# Drone.net
KiCad netlist of a schematic drawn in Altium Designer
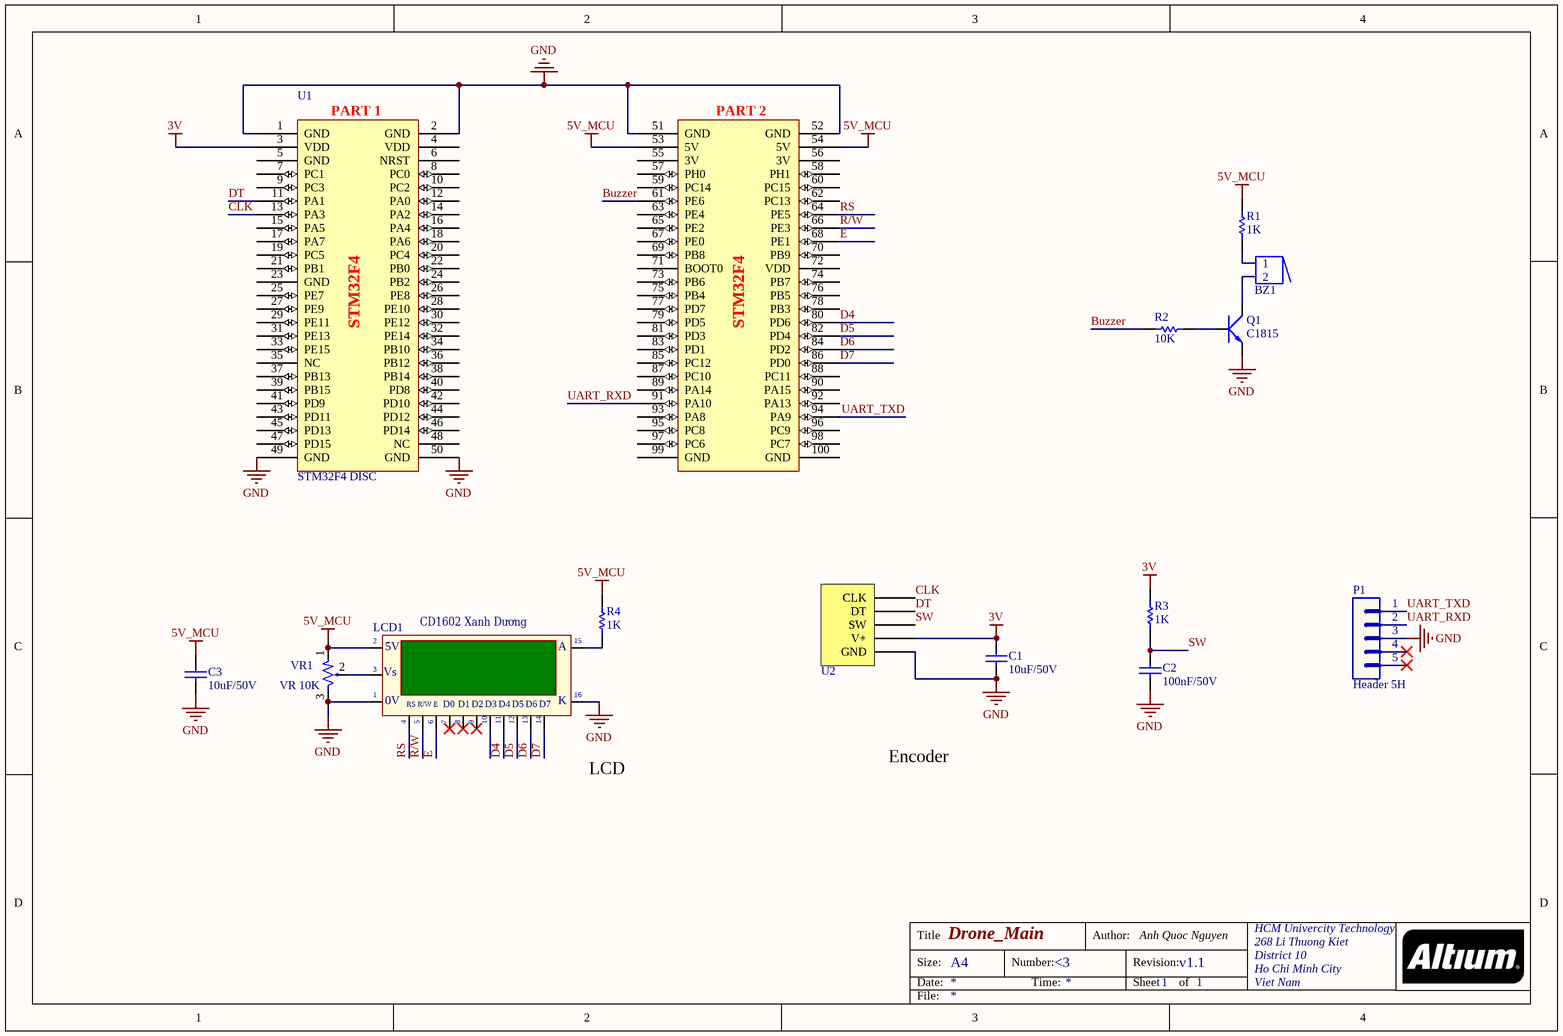
[diagram p0: Drone.SchDoc]

(export (version "E")
  (design (tool "Eeschema 10.0.6"))
  (components
    (comp (ref "BZ1") (value "Buzzer") (footprint "BUZZER") (libsource (lib "xecanbang") (part "Buzzer")))
    (comp (ref "C1")
      (value "10uF/50V")
      (footprint "CAP-SM-0805")
      (description "CAP CER 10UF 50V X5R 0805")
      (fields
        (field (name "MANUFACTURER") "Yageo")
        (field (name "MANUFACTURER PART NUMBER") "CC0805KKX5R9BB106")
      )
      (libsource (lib "Capacitor") (part "Cap-10uF-50V-0805"))
    )
    (comp (ref "C2")
      (value "100nF/50V")
      (footprint "CAP-SM-0805")
      (description "CAP CER 0.1UF 50V Y5V 0805")
      (fields
        (field (name "MANUFACTURER") "Samsung Electro-Mechanics")
        (field (name "MANUFACTURER PART NUMBER") "CL21F104ZBCNNNC")
      )
      (libsource (lib "Capacitor") (part "Cap-100nF-50V-0805"))
    )
    (comp (ref "C3")
      (value "10uF/50V")
      (footprint "CAP-SM-0805")
      (description "CAP CER 10UF 50V X5R 0805")
      (fields
        (field (name "MANUFACTURER") "Yageo")
        (field (name "MANUFACTURER PART NUMBER") "CC0805KKX5R9BB106")
      )
      (libsource (lib "Capacitor") (part "Cap-10uF-50V-0805"))
    )
    (comp (ref "LCD1")
      (value "CD1602 Xanh Dương")
      (footprint "LCD16X2")
      (description "Cắm")
      (libsource (lib "THU VIEN SCH") (part "LCD16x2A"))
    )
    (comp (ref "P1")
      (value "Header 5H")
      (footprint "JP5H")
      (description "Header, 5-Pin, Right Angle")
      (fields (field (name "PUBLISHER") "Altium Limited"))
      (libsource (lib "Header-connector") (part "Header 5H"))
    )
    (comp (ref "Q1")
      (value "C1815")
      (footprint "QTO-92")
      (description "Dán")
      (libsource (lib "THU VIEN SCH") (part "C1815"))
    )
    (comp (ref "R1")
      (value "1K")
      (footprint "Resistor:RES-SM-0805")
      (description "RES 1K OHM 1% 1/4W 0805")
      (fields
        (field (name "MANUFACTURER") "Stackpole Electronics Inc")
        (field (name "MANUFACTURER PART NUMBER") "RNCP0805FTD1K00")
      )
      (libsource (lib "Resistor") (part "Res-1K-0805"))
    )
    (comp (ref "R2")
      (value "10K")
      (footprint "Resistor:RES-SM-0805")
      (description "RES 10K OHM 1% 1/4W 0805")
      (fields
        (field (name "MANUFACTURER") "Stackpole Electronics Inc")
        (field (name "MANUFACTURER PART NUMBER") "RNCP0805FTD10K0")
      )
      (libsource (lib "Resistor") (part "Res-10k-0805"))
    )
    (comp (ref "R3")
      (value "1K")
      (footprint "Resistor:RES-SM-0805")
      (description "RES 1K OHM 1% 1/4W 0805")
      (fields
        (field (name "MANUFACTURER") "Stackpole Electronics Inc")
        (field (name "MANUFACTURER PART NUMBER") "RNCP0805FTD1K00")
      )
      (libsource (lib "Resistor") (part "Res-1K-0805"))
    )
    (comp (ref "R4")
      (value "1K")
      (footprint "Resistor:RES-SM-0805")
      (description "RES 1K OHM 1% 1/4W 0805")
      (fields
        (field (name "MANUFACTURER") "Stackpole Electronics Inc")
        (field (name "MANUFACTURER PART NUMBER") "RNCP0805FTD1K00")
      )
      (libsource (lib "Resistor") (part "Res-1K-0805"))
    )
    (comp (ref "U1")
      (value "STM32F4 DISC")
      (footprint "STM32F4 DISC")
      (description "STM32F4 Discovery board. Chip on Board is Stm32f411VET6. Speed is 150MHz")
      (libsource (lib "Drone") (part "STM32F4 DISC"))
    )
    (comp (ref "U2")
      (value "Rotary Encoder")
      (footprint "Rotary Encoder")
      (libsource (lib "Drone") (part "Rotary Encoder"))
    )
    (comp (ref "VR1")
      (value "VR 10K")
      (footprint "Varistor 1")
      (description "Var Resistor")
      (fields (field (name "Comment") "10K"))
      (libsource (lib "PIF_Library") (part "Var Resistor"))
    )
  )
  (nets
    (net (code "1") (name "/Buzzer") (class "Default")
      (node (ref "R2") (pin "1") (pinfunction "1_1") (pintype "passive"))
      (node (ref "U1") (pin "61") (pinfunction "PE6_61") (pintype "bidirectional"))
    )
    (net (code "2") (name "/CLK") (class "Default")
      (node (ref "U1") (pin "13") (pinfunction "PA3_13") (pintype "bidirectional"))
      (node (ref "U2") (pin "1") (pinfunction "CLK_1") (pintype "passive"))
    )
    (net (code "3") (name "/D4") (class "Default")
      (node (ref "LCD1") (pin "11") (pinfunction "D4_11") (pintype "passive"))
      (node (ref "U1") (pin "80") (pinfunction "PD6_80") (pintype "bidirectional"))
    )
    (net (code "4") (name "/D5") (class "Default")
      (node (ref "LCD1") (pin "12") (pinfunction "D5_12") (pintype "passive"))
      (node (ref "U1") (pin "82") (pinfunction "PD4_82") (pintype "bidirectional"))
    )
    (net (code "5") (name "/D6") (class "Default")
      (node (ref "LCD1") (pin "13") (pinfunction "D6_13") (pintype "passive"))
      (node (ref "U1") (pin "84") (pinfunction "PD2_84") (pintype "bidirectional"))
    )
    (net (code "6") (name "/D7") (class "Default")
      (node (ref "LCD1") (pin "14") (pinfunction "D7_14") (pintype "passive"))
      (node (ref "U1") (pin "86") (pinfunction "PD0_86") (pintype "bidirectional"))
    )
    (net (code "7") (name "/DT") (class "Default")
      (node (ref "U1") (pin "11") (pinfunction "PA1_11") (pintype "bidirectional"))
      (node (ref "U2") (pin "2") (pinfunction "DT_2") (pintype "passive"))
    )
    (net (code "8") (name "/E") (class "Default")
      (node (ref "LCD1") (pin "6") (pinfunction "~{EN}_6") (pintype "passive"))
      (node (ref "U1") (pin "68") (pinfunction "PE1_68") (pintype "bidirectional"))
    )
    (net (code "9") (name "/RS") (class "Default")
      (node (ref "LCD1") (pin "4") (pinfunction "RS_4") (pintype "passive"))
      (node (ref "U1") (pin "64") (pinfunction "PE5_64") (pintype "bidirectional"))
    )
    (net (code "10") (name "/R{slash}~{W}") (class "Default")
      (node (ref "LCD1") (pin "5") (pinfunction "R/~{W}_5") (pintype "passive"))
      (node (ref "U1") (pin "66") (pinfunction "PE3_66") (pintype "bidirectional"))
    )
    (net (code "11") (name "/SW") (class "Default")
      (node (ref "C2") (pin "2") (pinfunction "2_2") (pintype "passive"))
      (node (ref "R3") (pin "1") (pinfunction "1_1") (pintype "passive"))
      (node (ref "U2") (pin "3") (pinfunction "SW_3") (pintype "passive"))
    )
    (net (code "12") (name "/UART_RXD") (class "Default")
      (node (ref "P1") (pin "2") (pinfunction "2_2") (pintype "passive"))
      (node (ref "U1") (pin "91") (pinfunction "PA10_91") (pintype "bidirectional"))
    )
    (net (code "13") (name "/UART_TXD") (class "Default")
      (node (ref "P1") (pin "1") (pinfunction "1_1") (pintype "passive"))
      (node (ref "U1") (pin "94") (pinfunction "PA9_94") (pintype "bidirectional"))
    )
    (net (code "14") (name "3V") (class "Default")
      (node (ref "C1") (pin "1") (pinfunction "1_1") (pintype "passive"))
      (node (ref "R3") (pin "2") (pinfunction "2_2") (pintype "passive"))
      (node (ref "U1") (pin "3") (pinfunction "VDD_3") (pintype "power_in"))
      (node (ref "U2") (pin "4") (pinfunction "V+_4") (pintype "passive"))
    )
    (net (code "15") (name "5V_MCU") (class "Default")
      (node (ref "C3") (pin "1") (pinfunction "1_1") (pintype "passive"))
      (node (ref "LCD1") (pin "2") (pinfunction "VDD_2") (pintype "passive"))
      (node (ref "R1") (pin "2") (pinfunction "2_2") (pintype "passive"))
      (node (ref "R4") (pin "2") (pinfunction "2_2") (pintype "passive"))
      (node (ref "U1") (pin "53") (pinfunction "5V_53") (pintype "power_in"))
      (node (ref "U1") (pin "54") (pinfunction "5V_54") (pintype "power_in"))
      (node (ref "VR1") (pin "1") (pinfunction "1_1") (pintype "passive"))
    )
    (net (code "16") (name "GND") (class "Default")
      (node (ref "C1") (pin "2") (pinfunction "2_2") (pintype "passive"))
      (node (ref "C2") (pin "1") (pinfunction "1_1") (pintype "passive"))
      (node (ref "C3") (pin "2") (pinfunction "2_2") (pintype "passive"))
      (node (ref "LCD1") (pin "1") (pinfunction "GND_1") (pintype "passive"))
      (node (ref "LCD1") (pin "16") (pinfunction "K_16") (pintype "passive"))
      (node (ref "P1") (pin "3") (pinfunction "3_3") (pintype "passive"))
      (node (ref "Q1") (pin "3") (pinfunction "E_3") (pintype "passive"))
      (node (ref "U1") (pin "1") (pinfunction "GND_1") (pintype "power_in"))
      (node (ref "U1") (pin "2") (pinfunction "GND_2") (pintype "power_in"))
      (node (ref "U1") (pin "49") (pinfunction "GND_49") (pintype "power_in"))
      (node (ref "U1") (pin "50") (pinfunction "GND_50") (pintype "power_in"))
      (node (ref "U1") (pin "51") (pinfunction "GND_51") (pintype "power_in"))
      (node (ref "U1") (pin "52") (pinfunction "GND_52") (pintype "power_in"))
      (node (ref "U2") (pin "5") (pinfunction "GND_5") (pintype "passive"))
      (node (ref "VR1") (pin "3") (pinfunction "3_3") (pintype "passive"))
    )
    (net (code "17") (name "Net-(BZ1-Pad1)") (class "Default")
      (node (ref "BZ1") (pin "1") (pinfunction "1_1") (pintype "passive"))
      (node (ref "R1") (pin "1") (pinfunction "1_1") (pintype "passive"))
    )
    (net (code "18") (name "Net-(LCD1-A)") (class "Default")
      (node (ref "LCD1") (pin "15") (pinfunction "A_15") (pintype "passive"))
      (node (ref "R4") (pin "1") (pinfunction "1_1") (pintype "passive"))
    )
    (net (code "19") (name "Net-(LCD1-VEE)") (class "Default")
      (node (ref "LCD1") (pin "3") (pinfunction "VEE_3") (pintype "passive"))
      (node (ref "VR1") (pin "2") (pinfunction "2_2") (pintype "passive"))
    )
    (net (code "20") (name "Net-(Q1-B)") (class "Default")
      (node (ref "Q1") (pin "1") (pinfunction "B_1") (pintype "passive"))
      (node (ref "R2") (pin "2") (pinfunction "2_2") (pintype "passive"))
    )
    (net (code "21") (name "Net-(Q1-C)") (class "Default")
      (node (ref "BZ1") (pin "2") (pinfunction "2_2") (pintype "passive"))
      (node (ref "Q1") (pin "2") (pinfunction "C_2") (pintype "passive"))
    )
    (net (code "22") (name "unconnected-(LCD1-D0-Pad7)") (class "Default")
      (node (ref "LCD1") (pin "7") (pinfunction "D0_7") (pintype "passive+no_connect"))
    )
    (net (code "23") (name "unconnected-(LCD1-D1-Pad8)") (class "Default")
      (node (ref "LCD1") (pin "8") (pinfunction "D1_8") (pintype "passive+no_connect"))
    )
    (net (code "24") (name "unconnected-(LCD1-D2-Pad9)") (class "Default")
      (node (ref "LCD1") (pin "9") (pinfunction "D2_9") (pintype "passive+no_connect"))
    )
    (net (code "25") (name "unconnected-(LCD1-D3-Pad10)") (class "Default")
      (node (ref "LCD1") (pin "10") (pinfunction "D3_10") (pintype "passive"))
    )
    (net (code "26") (name "unconnected-(P1-Pad4)") (class "Default")
      (node (ref "P1") (pin "4") (pinfunction "4_4") (pintype "passive+no_connect"))
    )
    (net (code "27") (name "unconnected-(P1-Pad5)") (class "Default")
      (node (ref "P1") (pin "5") (pinfunction "5_5") (pintype "passive+no_connect"))
    )
    (net (code "28") (name "unconnected-(U1-3V-Pad55)") (class "Default")
      (node (ref "U1") (pin "55") (pinfunction "3V_55") (pintype "power_in"))
    )
    (net (code "29") (name "unconnected-(U1-3V-Pad56)") (class "Default")
      (node (ref "U1") (pin "56") (pinfunction "3V_56") (pintype "power_in"))
    )
    (net (code "30") (name "unconnected-(U1-BOOT0-Pad71)") (class "Default")
      (node (ref "U1") (pin "71") (pinfunction "BOOT0_71") (pintype "passive"))
    )
    (net (code "31") (name "unconnected-(U1-GND-Pad5)") (class "Default")
      (node (ref "U1") (pin "5") (pinfunction "GND_5") (pintype "power_in"))
    )
    (net (code "32") (name "unconnected-(U1-GND-Pad23)") (class "Default")
      (node (ref "U1") (pin "23") (pinfunction "GND_23") (pintype "power_in"))
    )
    (net (code "33") (name "unconnected-(U1-GND-Pad99)") (class "Default")
      (node (ref "U1") (pin "99") (pinfunction "GND_99") (pintype "power_in"))
    )
    (net (code "34") (name "unconnected-(U1-GND-Pad100)") (class "Default")
      (node (ref "U1") (pin "100") (pinfunction "GND_100") (pintype "power_in"))
    )
    (net (code "35") (name "unconnected-(U1-NC-Pad35)") (class "Default")
      (node (ref "U1") (pin "35") (pinfunction "NC_35") (pintype "passive"))
    )
    (net (code "36") (name "unconnected-(U1-NC-Pad48)") (class "Default")
      (node (ref "U1") (pin "48") (pinfunction "NC_48") (pintype "passive"))
    )
    (net (code "37") (name "unconnected-(U1-NRST-Pad6)") (class "Default")
      (node (ref "U1") (pin "6") (pinfunction "NRST_6") (pintype "passive"))
    )
    (net (code "38") (name "unconnected-(U1-PA0-Pad12)") (class "Default")
      (node (ref "U1") (pin "12") (pinfunction "PA0_12") (pintype "bidirectional"))
    )
    (net (code "39") (name "unconnected-(U1-PA2-Pad14)") (class "Default")
      (node (ref "U1") (pin "14") (pinfunction "PA2_14") (pintype "bidirectional"))
    )
    (net (code "40") (name "unconnected-(U1-PA4-Pad16)") (class "Default")
      (node (ref "U1") (pin "16") (pinfunction "PA4_16") (pintype "bidirectional"))
    )
    (net (code "41") (name "unconnected-(U1-PA5-Pad15)") (class "Default")
      (node (ref "U1") (pin "15") (pinfunction "PA5_15") (pintype "bidirectional"))
    )
    (net (code "42") (name "unconnected-(U1-PA6-Pad18)") (class "Default")
      (node (ref "U1") (pin "18") (pinfunction "PA6_18") (pintype "bidirectional"))
    )
    (net (code "43") (name "unconnected-(U1-PA7-Pad17)") (class "Default")
      (node (ref "U1") (pin "17") (pinfunction "PA7_17") (pintype "bidirectional"))
    )
    (net (code "44") (name "unconnected-(U1-PA8-Pad93)") (class "Default")
      (node (ref "U1") (pin "93") (pinfunction "PA8_93") (pintype "bidirectional"))
    )
    (net (code "45") (name "unconnected-(U1-PA13-Pad92)") (class "Default")
      (node (ref "U1") (pin "92") (pinfunction "PA13_92") (pintype "bidirectional"))
    )
    (net (code "46") (name "unconnected-(U1-PA14-Pad89)") (class "Default")
      (node (ref "U1") (pin "89") (pinfunction "PA14_89") (pintype "bidirectional"))
    )
    (net (code "47") (name "unconnected-(U1-PA15-Pad90)") (class "Default")
      (node (ref "U1") (pin "90") (pinfunction "PA15_90") (pintype "bidirectional"))
    )
    (net (code "48") (name "unconnected-(U1-PB0-Pad22)") (class "Default")
      (node (ref "U1") (pin "22") (pinfunction "PB0_22") (pintype "bidirectional"))
    )
    (net (code "49") (name "unconnected-(U1-PB1-Pad21)") (class "Default")
      (node (ref "U1") (pin "21") (pinfunction "PB1_21") (pintype "bidirectional"))
    )
    (net (code "50") (name "unconnected-(U1-PB2-Pad24)") (class "Default")
      (node (ref "U1") (pin "24") (pinfunction "PB2_24") (pintype "bidirectional"))
    )
    (net (code "51") (name "unconnected-(U1-PB3-Pad78)") (class "Default")
      (node (ref "U1") (pin "78") (pinfunction "PB3_78") (pintype "bidirectional"))
    )
    (net (code "52") (name "unconnected-(U1-PB4-Pad75)") (class "Default")
      (node (ref "U1") (pin "75") (pinfunction "PB4_75") (pintype "bidirectional"))
    )
    (net (code "53") (name "unconnected-(U1-PB5-Pad76)") (class "Default")
      (node (ref "U1") (pin "76") (pinfunction "PB5_76") (pintype "bidirectional"))
    )
    (net (code "54") (name "unconnected-(U1-PB6-Pad73)") (class "Default")
      (node (ref "U1") (pin "73") (pinfunction "PB6_73") (pintype "bidirectional"))
    )
    (net (code "55") (name "unconnected-(U1-PB7-Pad74)") (class "Default")
      (node (ref "U1") (pin "74") (pinfunction "PB7_74") (pintype "bidirectional"))
    )
    (net (code "56") (name "unconnected-(U1-PB8-Pad69)") (class "Default")
      (node (ref "U1") (pin "69") (pinfunction "PB8_69") (pintype "bidirectional"))
    )
    (net (code "57") (name "unconnected-(U1-PB9-Pad70)") (class "Default")
      (node (ref "U1") (pin "70") (pinfunction "PB9_70") (pintype "bidirectional"))
    )
    (net (code "58") (name "unconnected-(U1-PB10-Pad34)") (class "Default")
      (node (ref "U1") (pin "34") (pinfunction "PB10_34") (pintype "bidirectional"))
    )
    (net (code "59") (name "unconnected-(U1-PB12-Pad36)") (class "Default")
      (node (ref "U1") (pin "36") (pinfunction "PB12_36") (pintype "bidirectional"))
    )
    (net (code "60") (name "unconnected-(U1-PB13-Pad37)") (class "Default")
      (node (ref "U1") (pin "37") (pinfunction "PB13_37") (pintype "bidirectional"))
    )
    (net (code "61") (name "unconnected-(U1-PB14-Pad38)") (class "Default")
      (node (ref "U1") (pin "38") (pinfunction "PB14_38") (pintype "bidirectional"))
    )
    (net (code "62") (name "unconnected-(U1-PB15-Pad39)") (class "Default")
      (node (ref "U1") (pin "39") (pinfunction "PB15_39") (pintype "bidirectional"))
    )
    (net (code "63") (name "unconnected-(U1-PC0-Pad8)") (class "Default")
      (node (ref "U1") (pin "8") (pinfunction "PC0_8") (pintype "bidirectional"))
    )
    (net (code "64") (name "unconnected-(U1-PC1-Pad7)") (class "Default")
      (node (ref "U1") (pin "7") (pinfunction "PC1_7") (pintype "bidirectional"))
    )
    (net (code "65") (name "unconnected-(U1-PC2-Pad10)") (class "Default")
      (node (ref "U1") (pin "10") (pinfunction "PC2_10") (pintype "bidirectional"))
    )
    (net (code "66") (name "unconnected-(U1-PC3-Pad9)") (class "Default")
      (node (ref "U1") (pin "9") (pinfunction "PC3_9") (pintype "bidirectional"))
    )
    (net (code "67") (name "unconnected-(U1-PC4-Pad20)") (class "Default")
      (node (ref "U1") (pin "20") (pinfunction "PC4_20") (pintype "bidirectional"))
    )
    (net (code "68") (name "unconnected-(U1-PC5-Pad19)") (class "Default")
      (node (ref "U1") (pin "19") (pinfunction "PC5_19") (pintype "bidirectional"))
    )
    (net (code "69") (name "unconnected-(U1-PC6-Pad97)") (class "Default")
      (node (ref "U1") (pin "97") (pinfunction "PC6_97") (pintype "bidirectional"))
    )
    (net (code "70") (name "unconnected-(U1-PC7-Pad98)") (class "Default")
      (node (ref "U1") (pin "98") (pinfunction "PC7_98") (pintype "bidirectional"))
    )
    (net (code "71") (name "unconnected-(U1-PC8-Pad95)") (class "Default")
      (node (ref "U1") (pin "95") (pinfunction "PC8_95") (pintype "bidirectional"))
    )
    (net (code "72") (name "unconnected-(U1-PC9-Pad96)") (class "Default")
      (node (ref "U1") (pin "96") (pinfunction "PC9_96") (pintype "bidirectional"))
    )
    (net (code "73") (name "unconnected-(U1-PC10-Pad87)") (class "Default")
      (node (ref "U1") (pin "87") (pinfunction "PC10_87") (pintype "bidirectional"))
    )
    (net (code "74") (name "unconnected-(U1-PC11-Pad88)") (class "Default")
      (node (ref "U1") (pin "88") (pinfunction "PC11_88") (pintype "bidirectional"))
    )
    (net (code "75") (name "unconnected-(U1-PC12-Pad85)") (class "Default")
      (node (ref "U1") (pin "85") (pinfunction "PC12_85") (pintype "bidirectional"))
    )
    (net (code "76") (name "unconnected-(U1-PC13-Pad62)") (class "Default")
      (node (ref "U1") (pin "62") (pinfunction "PC13_62") (pintype "bidirectional"))
    )
    (net (code "77") (name "unconnected-(U1-PC14-Pad59)") (class "Default")
      (node (ref "U1") (pin "59") (pinfunction "PC14_59") (pintype "bidirectional"))
    )
    (net (code "78") (name "unconnected-(U1-PC15-Pad60)") (class "Default")
      (node (ref "U1") (pin "60") (pinfunction "PC15_60") (pintype "bidirectional"))
    )
    (net (code "79") (name "unconnected-(U1-PD1-Pad83)") (class "Default")
      (node (ref "U1") (pin "83") (pinfunction "PD1_83") (pintype "bidirectional"))
    )
    (net (code "80") (name "unconnected-(U1-PD3-Pad81)") (class "Default")
      (node (ref "U1") (pin "81") (pinfunction "PD3_81") (pintype "bidirectional"))
    )
    (net (code "81") (name "unconnected-(U1-PD5-Pad79)") (class "Default")
      (node (ref "U1") (pin "79") (pinfunction "PD5_79") (pintype "bidirectional"))
    )
    (net (code "82") (name "unconnected-(U1-PD7-Pad77)") (class "Default")
      (node (ref "U1") (pin "77") (pinfunction "PD7_77") (pintype "bidirectional"))
    )
    (net (code "83") (name "unconnected-(U1-PD8-Pad40)") (class "Default")
      (node (ref "U1") (pin "40") (pinfunction "PD8_40") (pintype "bidirectional"))
    )
    (net (code "84") (name "unconnected-(U1-PD9-Pad41)") (class "Default")
      (node (ref "U1") (pin "41") (pinfunction "PD9_41") (pintype "bidirectional"))
    )
    (net (code "85") (name "unconnected-(U1-PD10-Pad42)") (class "Default")
      (node (ref "U1") (pin "42") (pinfunction "PD10_42") (pintype "bidirectional"))
    )
    (net (code "86") (name "unconnected-(U1-PD11-Pad43)") (class "Default")
      (node (ref "U1") (pin "43") (pinfunction "PD11_43") (pintype "bidirectional"))
    )
    (net (code "87") (name "unconnected-(U1-PD12-Pad44)") (class "Default")
      (node (ref "U1") (pin "44") (pinfunction "PD12_44") (pintype "bidirectional"))
    )
    (net (code "88") (name "unconnected-(U1-PD13-Pad45)") (class "Default")
      (node (ref "U1") (pin "45") (pinfunction "PD13_45") (pintype "bidirectional"))
    )
    (net (code "89") (name "unconnected-(U1-PD14-Pad46)") (class "Default")
      (node (ref "U1") (pin "46") (pinfunction "PD14_46") (pintype "bidirectional"))
    )
    (net (code "90") (name "unconnected-(U1-PD15-Pad47)") (class "Default")
      (node (ref "U1") (pin "47") (pinfunction "PD15_47") (pintype "bidirectional"))
    )
    (net (code "91") (name "unconnected-(U1-PE0-Pad67)") (class "Default")
      (node (ref "U1") (pin "67") (pinfunction "PE0_67") (pintype "bidirectional"))
    )
    (net (code "92") (name "unconnected-(U1-PE2-Pad65)") (class "Default")
      (node (ref "U1") (pin "65") (pinfunction "PE2_65") (pintype "bidirectional"))
    )
    (net (code "93") (name "unconnected-(U1-PE4-Pad63)") (class "Default")
      (node (ref "U1") (pin "63") (pinfunction "PE4_63") (pintype "bidirectional"))
    )
    (net (code "94") (name "unconnected-(U1-PE7-Pad25)") (class "Default")
      (node (ref "U1") (pin "25") (pinfunction "PE7_25") (pintype "bidirectional"))
    )
    (net (code "95") (name "unconnected-(U1-PE8-Pad26)") (class "Default")
      (node (ref "U1") (pin "26") (pinfunction "PE8_26") (pintype "bidirectional"))
    )
    (net (code "96") (name "unconnected-(U1-PE9-Pad27)") (class "Default")
      (node (ref "U1") (pin "27") (pinfunction "PE9_27") (pintype "bidirectional"))
    )
    (net (code "97") (name "unconnected-(U1-PE10-Pad28)") (class "Default")
      (node (ref "U1") (pin "28") (pinfunction "PE10_28") (pintype "bidirectional"))
    )
    (net (code "98") (name "unconnected-(U1-PE11-Pad29)") (class "Default")
      (node (ref "U1") (pin "29") (pinfunction "PE11_29") (pintype "bidirectional"))
    )
    (net (code "99") (name "unconnected-(U1-PE12-Pad30)") (class "Default")
      (node (ref "U1") (pin "30") (pinfunction "PE12_30") (pintype "bidirectional"))
    )
    (net (code "100") (name "unconnected-(U1-PE13-Pad31)") (class "Default")
      (node (ref "U1") (pin "31") (pinfunction "PE13_31") (pintype "bidirectional"))
    )
    (net (code "101") (name "unconnected-(U1-PE14-Pad32)") (class "Default")
      (node (ref "U1") (pin "32") (pinfunction "PE14_32") (pintype "bidirectional"))
    )
    (net (code "102") (name "unconnected-(U1-PE15-Pad33)") (class "Default")
      (node (ref "U1") (pin "33") (pinfunction "PE15_33") (pintype "bidirectional"))
    )
    (net (code "103") (name "unconnected-(U1-PH0-Pad57)") (class "Default")
      (node (ref "U1") (pin "57") (pinfunction "PH0_57") (pintype "bidirectional"))
    )
    (net (code "104") (name "unconnected-(U1-PH1-Pad58)") (class "Default")
      (node (ref "U1") (pin "58") (pinfunction "PH1_58") (pintype "bidirectional"))
    )
    (net (code "105") (name "unconnected-(U1-VDD-Pad4)") (class "Default")
      (node (ref "U1") (pin "4") (pinfunction "VDD_4") (pintype "power_in"))
    )
    (net (code "106") (name "unconnected-(U1-VDD-Pad72)") (class "Default")
      (node (ref "U1") (pin "72") (pinfunction "VDD_72") (pintype "power_in"))
    )
  )
)
